# Amazing-All-Band-Receiver-New.net
KiCad netlist of a schematic drawn in EAGLE
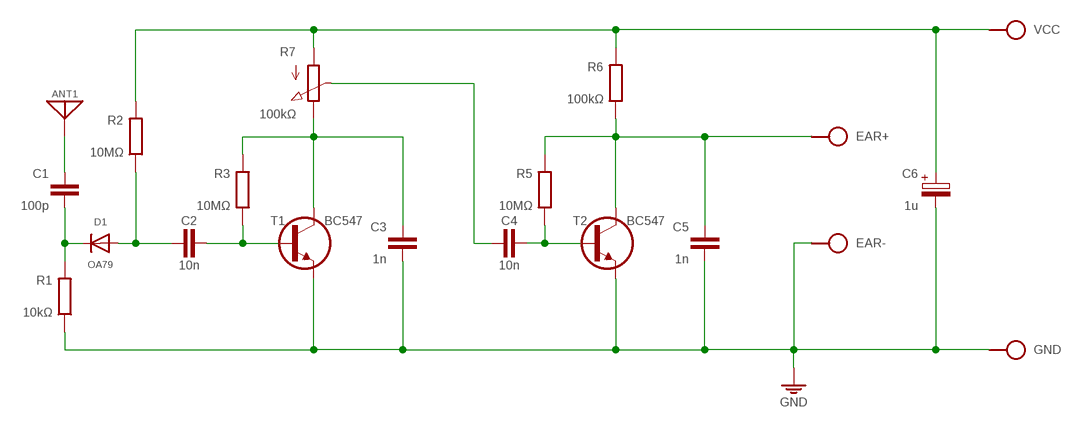
[diagram p0: schematic, sheet 1]

(export (version "E")
  (design (tool "Eeschema 10.0.6"))
  (components
    (comp (ref "ANT1")
      (value "ANT")
      (footprint "eagle-import:SPAD")
      (libsource (lib "eagle-import") (part "ANT"))
    )
    (comp (ref "C1")
      (value "100p")
      (footprint "eagle-import:C050-020X036_V")
      (libsource (lib "eagle-import") (part "C050-020X036/V"))
    )
    (comp (ref "C2")
      (value "10n")
      (footprint "eagle-import:C050-020X036")
      (libsource (lib "eagle-import") (part "C050-020X036"))
    )
    (comp (ref "C3")
      (value "1n")
      (footprint "eagle-import:C050-020X036")
      (libsource (lib "eagle-import") (part "C050-020X036"))
    )
    (comp (ref "C4")
      (value "10n")
      (footprint "eagle-import:C050-020X036")
      (libsource (lib "eagle-import") (part "C050-020X036"))
    )
    (comp (ref "C5")
      (value "1n")
      (footprint "eagle-import:C050-020X036")
      (libsource (lib "eagle-import") (part "C050-020X036"))
    )
    (comp (ref "C6")
      (value "1u")
      (footprint "eagle-import:E2,5-3")
      (libsource (lib "eagle-import") (part "CPOLE2,5-3"))
    )
    (comp (ref "D1")
      (value "OA79")
      (footprint "eagle-import:DO34-7V")
      (libsource (lib "eagle-import") (part "1N414834-7V"))
    )
    (comp (ref "EAR+")
      (value "SPAD")
      (footprint "eagle-import:SPAD")
      (libsource (lib "eagle-import") (part "SPAD"))
    )
    (comp (ref "EAR-")
      (value "SPAD")
      (footprint "eagle-import:SPAD")
      (libsource (lib "eagle-import") (part "SPAD"))
    )
    (comp (ref "GND")
      (value "SPAD")
      (footprint "eagle-import:SPAD")
      (libsource (lib "eagle-import") (part "SPAD"))
    )
    (comp (ref "R1")
      (value "10kΩ")
      (footprint "eagle-import:0202_7-V")
      (libsource (lib "eagle-import") (part "R0202/7-V"))
    )
    (comp (ref "R2")
      (value "10MΩ")
      (footprint "eagle-import:0202_7")
      (libsource (lib "eagle-import") (part "R0202/7"))
    )
    (comp (ref "R3")
      (value "10MΩ")
      (footprint "eagle-import:0202_7-V")
      (libsource (lib "eagle-import") (part "R0202/7-V"))
    )
    (comp (ref "R5")
      (value "10MΩ")
      (footprint "eagle-import:0202_7-V")
      (libsource (lib "eagle-import") (part "R0202/7-V"))
    )
    (comp (ref "R6")
      (value "100kΩ")
      (footprint "eagle-import:0202_7-V")
      (libsource (lib "eagle-import") (part "R0202/7-V"))
    )
    (comp (ref "R7")
      (value "100kΩ")
      (footprint "eagle-import:POT")
      (libsource (lib "eagle-import") (part "POT"))
    )
    (comp (ref "T1")
      (value "BC547")
      (footprint "eagle-import:TO92-CBE")
      (libsource (lib "eagle-import") (part "BC547CBE"))
    )
    (comp (ref "T2")
      (value "BC547")
      (footprint "eagle-import:TO92-CBE")
      (libsource (lib "eagle-import") (part "BC547CBE"))
    )
    (comp (ref "VCC")
      (value "SPAD")
      (footprint "eagle-import:SPAD")
      (libsource (lib "eagle-import") (part "SPAD"))
    )
  )
  (nets
    (net (code "1") (name "GND") (class "Default")
      (node (ref "C3") (pin "2") (pinfunction "2_2") (pintype "passive"))
      (node (ref "C5") (pin "2") (pinfunction "2_2") (pintype "passive"))
      (node (ref "C6") (pin "-") (pinfunction "-_-") (pintype "passive"))
      (node (ref "EAR-") (pin "1") (pinfunction "P$1_1") (pintype "bidirectional"))
      (node (ref "GND") (pin "1") (pinfunction "P$1_1") (pintype "bidirectional"))
      (node (ref "R1") (pin "1") (pinfunction "1_1") (pintype "passive"))
      (node (ref "T1") (pin "E") (pinfunction "E_E") (pintype "passive"))
      (node (ref "T2") (pin "E") (pinfunction "E_E") (pintype "passive"))
    )
    (net (code "2") (name "Net-(ANT1-Pad1)") (class "Default")
      (node (ref "ANT1") (pin "1") (pinfunction "1_1") (pintype "output"))
      (node (ref "C1") (pin "1") (pinfunction "1_1") (pintype "passive"))
    )
    (net (code "3") (name "Net-(C1-Pad2)") (class "Default")
      (node (ref "C1") (pin "2") (pinfunction "2_2") (pintype "passive"))
      (node (ref "D1") (pin "C") (pinfunction "C_C") (pintype "passive"))
      (node (ref "R1") (pin "2") (pinfunction "2_2") (pintype "passive"))
    )
    (net (code "4") (name "Net-(C2-Pad1)") (class "Default")
      (node (ref "C2") (pin "1") (pinfunction "1_1") (pintype "passive"))
      (node (ref "R3") (pin "1") (pinfunction "1_1") (pintype "passive"))
      (node (ref "T1") (pin "B") (pinfunction "B_B") (pintype "passive"))
    )
    (net (code "5") (name "Net-(C2-Pad2)") (class "Default")
      (node (ref "C2") (pin "2") (pinfunction "2_2") (pintype "passive"))
      (node (ref "D1") (pin "A") (pinfunction "A_A") (pintype "passive"))
      (node (ref "R2") (pin "1") (pinfunction "1_1") (pintype "passive"))
    )
    (net (code "6") (name "Net-(C4-Pad1)") (class "Default")
      (node (ref "C4") (pin "1") (pinfunction "1_1") (pintype "passive"))
      (node (ref "R5") (pin "1") (pinfunction "1_1") (pintype "passive"))
      (node (ref "T2") (pin "B") (pinfunction "B_B") (pintype "passive"))
    )
    (net (code "7") (name "Net-(EAR+-P$1)") (class "Default")
      (node (ref "C5") (pin "1") (pinfunction "1_1") (pintype "passive"))
      (node (ref "EAR+") (pin "1") (pinfunction "P$1_1") (pintype "bidirectional"))
      (node (ref "R5") (pin "2") (pinfunction "2_2") (pintype "passive"))
      (node (ref "R6") (pin "1") (pinfunction "1_1") (pintype "passive"))
      (node (ref "T2") (pin "C") (pinfunction "C_C") (pintype "passive"))
    )
    (net (code "8") (name "Net-(R7-A)") (class "Default")
      (node (ref "C6") (pin "+") (pinfunction "+_+") (pintype "passive"))
      (node (ref "R2") (pin "2") (pinfunction "2_2") (pintype "passive"))
      (node (ref "R6") (pin "2") (pinfunction "2_2") (pintype "passive"))
      (node (ref "R7") (pin "1") (pinfunction "A_1") (pintype "passive"))
      (node (ref "VCC") (pin "1") (pinfunction "P$1_1") (pintype "bidirectional"))
    )
    (net (code "9") (name "Net-(R7-E)") (class "Default")
      (node (ref "C3") (pin "1") (pinfunction "1_1") (pintype "passive"))
      (node (ref "R3") (pin "2") (pinfunction "2_2") (pintype "passive"))
      (node (ref "R7") (pin "3") (pinfunction "E_3") (pintype "passive"))
      (node (ref "T1") (pin "C") (pinfunction "C_C") (pintype "passive"))
    )
    (net (code "10") (name "Net-(R7-S)") (class "Default")
      (node (ref "C4") (pin "2") (pinfunction "2_2") (pintype "passive"))
      (node (ref "R7") (pin "2") (pinfunction "S_2") (pintype "passive"))
    )
  )
)
